# Extern.net
KiCad netlist of a schematic drawn in EAGLE
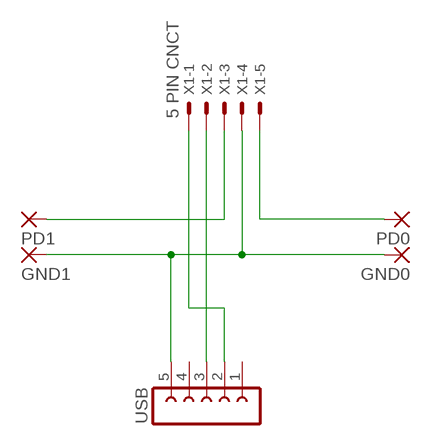
[diagram p0: schematic, sheet 1]

(export (version "E")
  (design (tool "Eeschema 10.0.6"))
  (components
    (comp (ref "GND0")
      (value "SMD5")
      (footprint "eagle-import:SMD2,54-5,08")
      (libsource (lib "eagle-import") (part "SMD5"))
    )
    (comp (ref "GND1")
      (value "SMD5")
      (footprint "eagle-import:SMD2,54-5,08")
      (libsource (lib "eagle-import") (part "SMD5"))
    )
    (comp (ref "PD0")
      (value "SMD5")
      (footprint "eagle-import:SMD2,54-5,08")
      (libsource (lib "eagle-import") (part "SMD5"))
    )
    (comp (ref "PD1")
      (value "SMD5")
      (footprint "eagle-import:SMD2,54-5,08")
      (libsource (lib "eagle-import") (part "SMD5"))
    )
    (comp (ref "USB")
      (value "FE05-1")
      (footprint "eagle-import:FE05-1")
      (libsource (lib "eagle-import") (part "FE05-1"))
    )
    (comp (ref "X1")
      (value "5 PIN CNCT")
      (footprint "eagle-import:JST-XH-05-PACKAGE-ROUND-PAD")
      (libsource (lib "eagle-import") (part "JST-XH-05-PIN-ROUND-PAD"))
    )
  )
  (nets
    (net (code "1") (name "Net-(GND0-P)") (class "Default")
      (node (ref "GND0") (pin "1") (pinfunction "P_1") (pintype "passive"))
      (node (ref "GND1") (pin "1") (pinfunction "P_1") (pintype "passive"))
      (node (ref "USB") (pin "5") (pinfunction "5_5") (pintype "passive"))
      (node (ref "X1") (pin "4") (pinfunction "S_4") (pintype "passive"))
    )
    (net (code "2") (name "Net-(PD0-P)") (class "Default")
      (node (ref "PD0") (pin "1") (pinfunction "P_1") (pintype "passive"))
      (node (ref "X1") (pin "5") (pinfunction "S_5") (pintype "passive"))
    )
    (net (code "3") (name "Net-(PD1-P)") (class "Default")
      (node (ref "PD1") (pin "1") (pinfunction "P_1") (pintype "passive"))
      (node (ref "X1") (pin "3") (pinfunction "S_3") (pintype "passive"))
    )
    (net (code "4") (name "Net-(X1A-S)") (class "Default")
      (node (ref "USB") (pin "2") (pinfunction "2_2") (pintype "passive"))
      (node (ref "X1") (pin "1") (pinfunction "S_1") (pintype "passive"))
    )
    (net (code "5") (name "Net-(X1B-S)") (class "Default")
      (node (ref "USB") (pin "3") (pinfunction "3_3") (pintype "passive"))
      (node (ref "X1") (pin "2") (pinfunction "S_2") (pintype "passive"))
    )
    (net (code "6") (name "unconnected-(USB-Pad1)") (class "Default")
      (node (ref "USB") (pin "1") (pinfunction "1_1") (pintype "passive"))
    )
    (net (code "7") (name "unconnected-(USB-Pad4)") (class "Default")
      (node (ref "USB") (pin "4") (pinfunction "4_4") (pintype "passive"))
    )
  )
)
